# SY_HR08_MCU_CTL_V1_1.net
KiCad netlist of a schematic drawn in Altium Designer
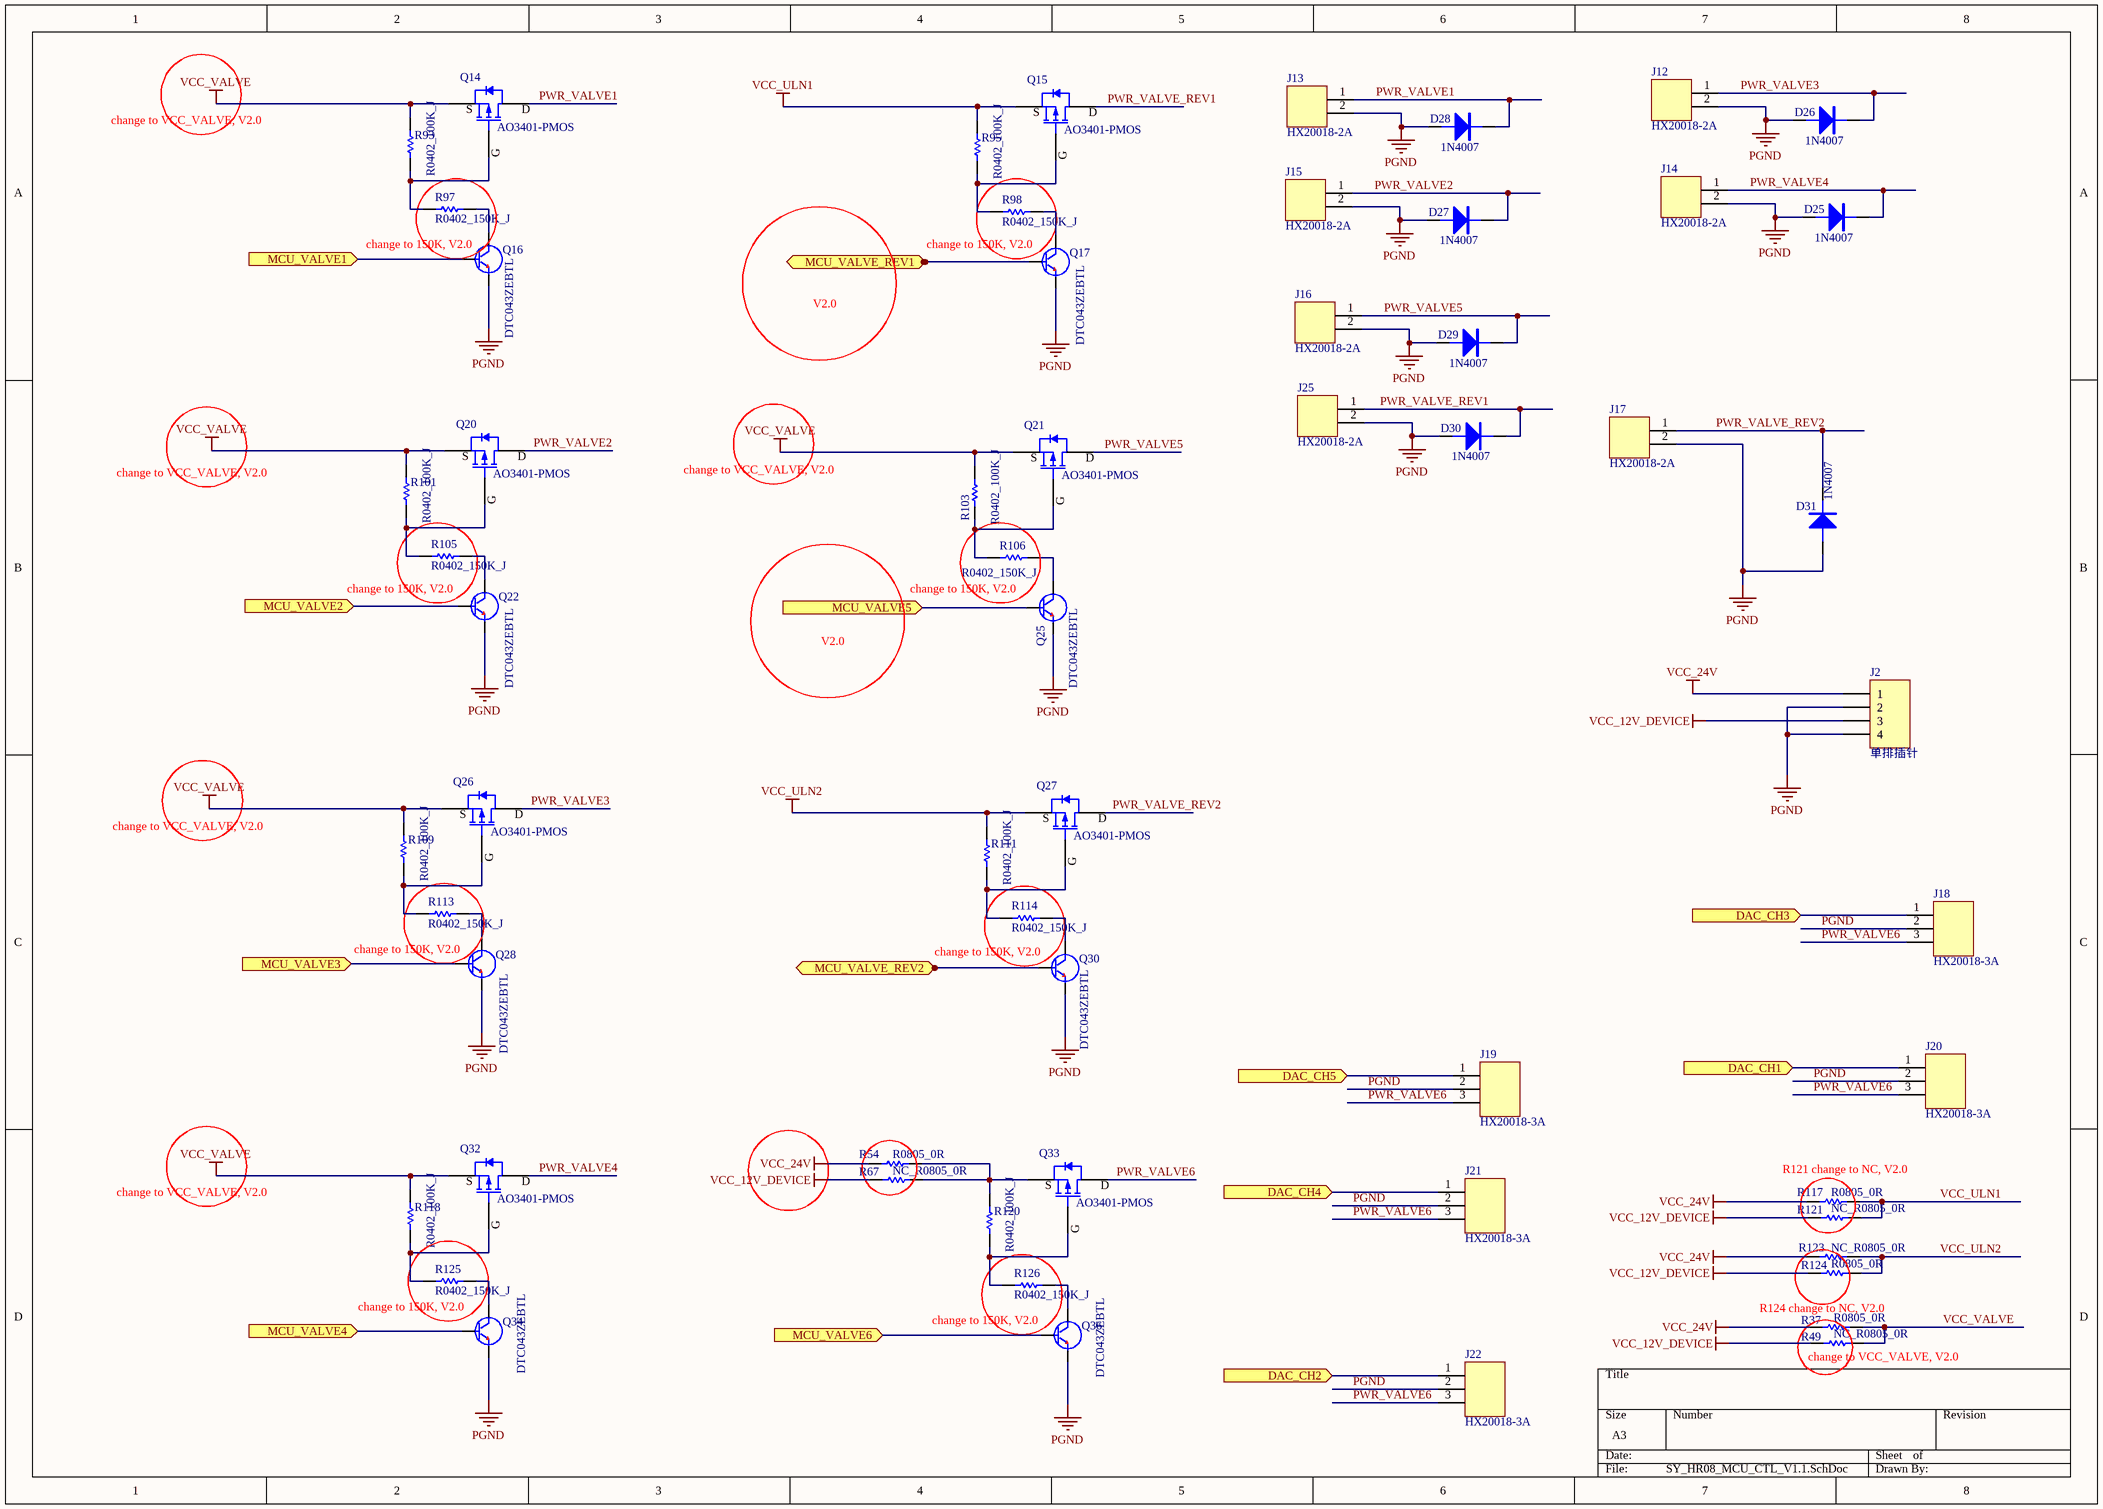
[diagram p0: SY_HR08_MCU_CTL_V1.1.SchDoc]

(export (version "E")
  (design (tool "Eeschema 10.0.6"))
  (components
    (comp (ref "D25")
      (value "1N4007")
      (footprint "1N4007")
      (description "1N4007 整流二极管 1A 1000V")
      (libsource (lib "zhangky_sch") (part "1N4007"))
    )
    (comp (ref "D26")
      (value "1N4007")
      (footprint "1N4007")
      (description "1N4007 整流二极管 1A 1000V")
      (libsource (lib "zhangky_sch") (part "1N4007"))
    )
    (comp (ref "D27")
      (value "1N4007")
      (footprint "1N4007")
      (description "1N4007 整流二极管 1A 1000V")
      (libsource (lib "zhangky_sch") (part "1N4007"))
    )
    (comp (ref "D28")
      (value "1N4007")
      (footprint "1N4007")
      (description "1N4007 整流二极管 1A 1000V")
      (libsource (lib "zhangky_sch") (part "1N4007"))
    )
    (comp (ref "D29")
      (value "1N4007")
      (footprint "1N4007")
      (description "1N4007 整流二极管 1A 1000V")
      (libsource (lib "zhangky_sch") (part "1N4007"))
    )
    (comp (ref "D30")
      (value "1N4007")
      (footprint "1N4007")
      (description "1N4007 整流二极管 1A 1000V")
      (libsource (lib "zhangky_sch") (part "1N4007"))
    )
    (comp (ref "D31")
      (value "1N4007")
      (footprint "1N4007")
      (description "1N4007 整流二极管 1A 1000V")
      (libsource (lib "zhangky_sch") (part "1N4007"))
    )
    (comp (ref "J2")
      (value "单排插针")
      (footprint "CON1X4(2.54mm)")
      (description "Header, 4-Pin")
      (fields (field (name "PUBLISHER") "Altium Limited"))
      (libsource (lib "YS-F1Pro开发板主板") (part "Header 4"))
    )
    (comp (ref "J12")
      (value "HX20018-2A")
      (footprint "HX20018-2A")
      (description "HX20018-2A  2.0mm")
      (libsource (lib "zhangky_sch") (part "HX20018-2A"))
    )
    (comp (ref "J13")
      (value "HX20018-2A")
      (footprint "HX20018-2A")
      (description "HX20018-2A  2.0mm")
      (libsource (lib "zhangky_sch") (part "HX20018-2A"))
    )
    (comp (ref "J14")
      (value "HX20018-2A")
      (footprint "HX20018-2A")
      (description "HX20018-2A  2.0mm")
      (libsource (lib "zhangky_sch") (part "HX20018-2A"))
    )
    (comp (ref "J15")
      (value "HX20018-2A")
      (footprint "HX20018-2A")
      (description "HX20018-2A  2.0mm")
      (libsource (lib "zhangky_sch") (part "HX20018-2A"))
    )
    (comp (ref "J16")
      (value "HX20018-2A")
      (footprint "HX20018-2A")
      (description "HX20018-2A  2.0mm")
      (libsource (lib "zhangky_sch") (part "HX20018-2A"))
    )
    (comp (ref "J17")
      (value "HX20018-2A")
      (footprint "HX20018-2A")
      (description "HX20018-2A  2.0mm")
      (libsource (lib "zhangky_sch") (part "HX20018-2A"))
    )
    (comp (ref "J18")
      (value "HX20018-3A")
      (footprint "HX20018-3A")
      (description "HX20018-3A  2.0mm")
      (libsource (lib "zhangky_sch") (part "HX20018-3A"))
    )
    (comp (ref "J19")
      (value "HX20018-3A")
      (footprint "HX20018-3A")
      (description "HX20018-3A  2.0mm")
      (libsource (lib "zhangky_sch") (part "HX20018-3A"))
    )
    (comp (ref "J20")
      (value "HX20018-3A")
      (footprint "HX20018-3A")
      (description "HX20018-3A  2.0mm")
      (libsource (lib "zhangky_sch") (part "HX20018-3A"))
    )
    (comp (ref "J21")
      (value "HX20018-3A")
      (footprint "HX20018-3A")
      (description "HX20018-3A  2.0mm")
      (libsource (lib "zhangky_sch") (part "HX20018-3A"))
    )
    (comp (ref "J22")
      (value "HX20018-3A")
      (footprint "HX20018-3A")
      (description "HX20018-3A  2.0mm")
      (libsource (lib "zhangky_sch") (part "HX20018-3A"))
    )
    (comp (ref "J25")
      (value "HX20018-2A")
      (footprint "HX20018-2A")
      (description "HX20018-2A  2.0mm")
      (libsource (lib "zhangky_sch") (part "HX20018-2A"))
    )
    (comp (ref "Q14")
      (value "AO3401-PMOS")
      (footprint "AO3400")
      (libsource (lib "zhangky_sch") (part "AO3401-PMOS"))
    )
    (comp (ref "Q15")
      (value "AO3401-PMOS")
      (footprint "AO3400")
      (libsource (lib "zhangky_sch") (part "AO3401-PMOS"))
    )
    (comp (ref "Q16")
      (value "DTC043ZEBTL")
      (footprint "DTC043ZEBTL$2F$$2F$DTC143ZE$2F$$2F$LDTC143ZET1G")
      (description "NPN三极管_100mA_EMT3F")
      (libsource (lib "zhangky_sch") (part "DTC043ZEBTL"))
    )
    (comp (ref "Q17")
      (value "DTC043ZEBTL")
      (footprint "DTC043ZEBTL$2F$$2F$DTC143ZE$2F$$2F$LDTC143ZET1G")
      (description "NPN三极管_100mA_EMT3F")
      (libsource (lib "zhangky_sch") (part "DTC043ZEBTL"))
    )
    (comp (ref "Q20")
      (value "AO3401-PMOS")
      (footprint "AO3400")
      (libsource (lib "zhangky_sch") (part "AO3401-PMOS"))
    )
    (comp (ref "Q21")
      (value "AO3401-PMOS")
      (footprint "AO3400")
      (libsource (lib "zhangky_sch") (part "AO3401-PMOS"))
    )
    (comp (ref "Q22")
      (value "DTC043ZEBTL")
      (footprint "DTC043ZEBTL$2F$$2F$DTC143ZE$2F$$2F$LDTC143ZET1G")
      (description "NPN三极管_100mA_EMT3F")
      (libsource (lib "zhangky_sch") (part "DTC043ZEBTL"))
    )
    (comp (ref "Q25")
      (value "DTC043ZEBTL")
      (footprint "DTC043ZEBTL$2F$$2F$DTC143ZE$2F$$2F$LDTC143ZET1G")
      (description "NPN三极管_100mA_EMT3F")
      (libsource (lib "zhangky_sch") (part "DTC043ZEBTL"))
    )
    (comp (ref "Q26")
      (value "AO3401-PMOS")
      (footprint "AO3400")
      (libsource (lib "zhangky_sch") (part "AO3401-PMOS"))
    )
    (comp (ref "Q27")
      (value "AO3401-PMOS")
      (footprint "AO3400")
      (libsource (lib "zhangky_sch") (part "AO3401-PMOS"))
    )
    (comp (ref "Q28")
      (value "DTC043ZEBTL")
      (footprint "DTC043ZEBTL$2F$$2F$DTC143ZE$2F$$2F$LDTC143ZET1G")
      (description "NPN三极管_100mA_EMT3F")
      (libsource (lib "zhangky_sch") (part "DTC043ZEBTL"))
    )
    (comp (ref "Q30")
      (value "DTC043ZEBTL")
      (footprint "DTC043ZEBTL$2F$$2F$DTC143ZE$2F$$2F$LDTC143ZET1G")
      (description "NPN三极管_100mA_EMT3F")
      (libsource (lib "zhangky_sch") (part "DTC043ZEBTL"))
    )
    (comp (ref "Q32")
      (value "AO3401-PMOS")
      (footprint "AO3400")
      (libsource (lib "zhangky_sch") (part "AO3401-PMOS"))
    )
    (comp (ref "Q33")
      (value "AO3401-PMOS")
      (footprint "AO3400")
      (libsource (lib "zhangky_sch") (part "AO3401-PMOS"))
    )
    (comp (ref "Q34")
      (value "DTC043ZEBTL")
      (footprint "DTC043ZEBTL$2F$$2F$DTC143ZE$2F$$2F$LDTC143ZET1G")
      (description "NPN三极管_100mA_EMT3F")
      (libsource (lib "zhangky_sch") (part "DTC043ZEBTL"))
    )
    (comp (ref "Q36")
      (value "DTC043ZEBTL")
      (footprint "DTC043ZEBTL$2F$$2F$DTC143ZE$2F$$2F$LDTC143ZET1G")
      (description "NPN三极管_100mA_EMT3F")
      (libsource (lib "zhangky_sch") (part "DTC043ZEBTL"))
    )
    (comp (ref "R37")
      (value "R0805_0R")
      (footprint "RES0805")
      (description "电阻0R(0805-0.125W-J)")
      (libsource (lib "zhangky_sch") (part "R0805_0R"))
    )
    (comp (ref "R49")
      (value "NC_R0805_0R")
      (footprint "RES0805")
      (description "电阻0R(0805-0.125W-J)")
      (libsource (lib "zhangky_sch") (part "R0805_0R"))
    )
    (comp (ref "R54")
      (value "R0805_0R")
      (footprint "RES0805")
      (description "电阻0R(0805-0.125W-J)")
      (libsource (lib "zhangky_sch") (part "R0805_0R"))
    )
    (comp (ref "R67")
      (value "NC_R0805_0R")
      (footprint "RES0805")
      (description "电阻0R(0805-0.125W-J)")
      (libsource (lib "zhangky_sch") (part "R0805_0R"))
    )
    (comp (ref "R93")
      (value "R0402_100K_J")
      (footprint "RES0402_HQ")
      (description "电阻100K(0402-0.0625W-J)")
      (libsource (lib "zhangky_sch") (part "R0402_100K_J"))
    )
    (comp (ref "R95")
      (value "R0402_100K_J")
      (footprint "RES0402_HQ")
      (description "电阻100K(0402-0.0625W-J)")
      (libsource (lib "zhangky_sch") (part "R0402_100K_J"))
    )
    (comp (ref "R97")
      (value "R0402_150K_J")
      (footprint "RES0402_HQ")
      (description "电阻100K(0402-0.0625W-J)")
      (libsource (lib "zhangky_sch") (part "R0402_100K_J"))
    )
    (comp (ref "R98")
      (value "R0402_150K_J")
      (footprint "RES0402_HQ")
      (description "电阻100K(0402-0.0625W-J)")
      (libsource (lib "zhangky_sch") (part "R0402_100K_J"))
    )
    (comp (ref "R101")
      (value "R0402_100K_J")
      (footprint "RES0402_HQ")
      (description "电阻100K(0402-0.0625W-J)")
      (libsource (lib "zhangky_sch") (part "R0402_100K_J"))
    )
    (comp (ref "R103")
      (value "R0402_100K_J")
      (footprint "RES0402_HQ")
      (description "电阻100K(0402-0.0625W-J)")
      (libsource (lib "zhangky_sch") (part "R0402_100K_J"))
    )
    (comp (ref "R105")
      (value "R0402_150K_J")
      (footprint "RES0402_HQ")
      (description "电阻100K(0402-0.0625W-J)")
      (libsource (lib "zhangky_sch") (part "R0402_100K_J"))
    )
    (comp (ref "R106")
      (value "R0402_150K_J")
      (footprint "RES0402_HQ")
      (description "电阻100K(0402-0.0625W-J)")
      (libsource (lib "zhangky_sch") (part "R0402_100K_J"))
    )
    (comp (ref "R109")
      (value "R0402_100K_J")
      (footprint "RES0402_HQ")
      (description "电阻100K(0402-0.0625W-J)")
      (libsource (lib "zhangky_sch") (part "R0402_100K_J"))
    )
    (comp (ref "R111")
      (value "R0402_100K_J")
      (footprint "RES0402_HQ")
      (description "电阻100K(0402-0.0625W-J)")
      (libsource (lib "zhangky_sch") (part "R0402_100K_J"))
    )
    (comp (ref "R113")
      (value "R0402_150K_J")
      (footprint "RES0402_HQ")
      (description "电阻100K(0402-0.0625W-J)")
      (libsource (lib "zhangky_sch") (part "R0402_100K_J"))
    )
    (comp (ref "R114")
      (value "R0402_150K_J")
      (footprint "RES0402_HQ")
      (description "电阻100K(0402-0.0625W-J)")
      (libsource (lib "zhangky_sch") (part "R0402_100K_J"))
    )
    (comp (ref "R117")
      (value "R0805_0R")
      (footprint "RES0805")
      (description "电阻0R(0805-0.125W-J)")
      (libsource (lib "zhangky_sch") (part "R0805_0R"))
    )
    (comp (ref "R118")
      (value "R0402_100K_J")
      (footprint "RES0402_HQ")
      (description "电阻100K(0402-0.0625W-J)")
      (libsource (lib "zhangky_sch") (part "R0402_100K_J"))
    )
    (comp (ref "R120")
      (value "R0402_100K_J")
      (footprint "RES0402_HQ")
      (description "电阻100K(0402-0.0625W-J)")
      (libsource (lib "zhangky_sch") (part "R0402_100K_J"))
    )
    (comp (ref "R121")
      (value "NC_R0805_0R")
      (footprint "RES0805")
      (description "电阻0R(0805-0.125W-J)")
      (libsource (lib "zhangky_sch") (part "R0805_0R"))
    )
    (comp (ref "R123")
      (value "NC_R0805_0R")
      (footprint "RES0805")
      (description "电阻0R(0805-0.125W-J)")
      (libsource (lib "zhangky_sch") (part "R0805_0R"))
    )
    (comp (ref "R124")
      (value "R0805_0R")
      (footprint "RES0805")
      (description "电阻0R(0805-0.125W-J)")
      (libsource (lib "zhangky_sch") (part "R0805_0R"))
    )
    (comp (ref "R125")
      (value "R0402_150K_J")
      (footprint "RES0402_HQ")
      (description "电阻100K(0402-0.0625W-J)")
      (libsource (lib "zhangky_sch") (part "R0402_100K_J"))
    )
    (comp (ref "R126")
      (value "R0402_150K_J")
      (footprint "RES0402_HQ")
      (description "电阻100K(0402-0.0625W-J)")
      (libsource (lib "zhangky_sch") (part "R0402_100K_J"))
    )
  )
  (nets
    (net (code "1") (name "/DAC_CH1") (class "Default")
      (node (ref "J20") (pin "1") (pinfunction "1_1") (pintype "passive"))
    )
    (net (code "2") (name "/DAC_CH2") (class "Default")
      (node (ref "J22") (pin "1") (pinfunction "1_1") (pintype "passive"))
    )
    (net (code "3") (name "/DAC_CH3") (class "Default")
      (node (ref "J18") (pin "1") (pinfunction "1_1") (pintype "passive"))
    )
    (net (code "4") (name "/DAC_CH4") (class "Default")
      (node (ref "J21") (pin "1") (pinfunction "1_1") (pintype "passive"))
    )
    (net (code "5") (name "/DAC_CH5") (class "Default")
      (node (ref "J19") (pin "1") (pinfunction "1_1") (pintype "passive"))
    )
    (net (code "6") (name "/MCU_VALVE1") (class "Default")
      (node (ref "Q16") (pin "1") (pinfunction "B_1") (pintype "passive"))
    )
    (net (code "7") (name "/MCU_VALVE2") (class "Default")
      (node (ref "Q22") (pin "1") (pinfunction "B_1") (pintype "passive"))
    )
    (net (code "8") (name "/MCU_VALVE3") (class "Default")
      (node (ref "Q28") (pin "1") (pinfunction "B_1") (pintype "passive"))
    )
    (net (code "9") (name "/MCU_VALVE4") (class "Default")
      (node (ref "Q34") (pin "1") (pinfunction "B_1") (pintype "passive"))
    )
    (net (code "10") (name "/MCU_VALVE5") (class "Default")
      (node (ref "Q25") (pin "1") (pinfunction "B_1") (pintype "passive"))
    )
    (net (code "11") (name "/MCU_VALVE6") (class "Default")
      (node (ref "Q36") (pin "1") (pinfunction "B_1") (pintype "passive"))
    )
    (net (code "12") (name "/MCU_VALVE_REV1") (class "Default")
      (node (ref "Q17") (pin "1") (pinfunction "B_1") (pintype "passive"))
    )
    (net (code "13") (name "/MCU_VALVE_REV2") (class "Default")
      (node (ref "Q30") (pin "1") (pinfunction "B_1") (pintype "passive"))
    )
    (net (code "14") (name "/PWR_VALVE1") (class "Default")
      (node (ref "D28") (pin "1") (pinfunction "1_1") (pintype "passive"))
      (node (ref "J13") (pin "1") (pinfunction "1_1") (pintype "passive"))
      (node (ref "Q14") (pin "3") (pinfunction "D_3") (pintype "passive"))
    )
    (net (code "15") (name "/PWR_VALVE2") (class "Default")
      (node (ref "D27") (pin "1") (pinfunction "1_1") (pintype "passive"))
      (node (ref "J15") (pin "1") (pinfunction "1_1") (pintype "passive"))
      (node (ref "Q20") (pin "3") (pinfunction "D_3") (pintype "passive"))
    )
    (net (code "16") (name "/PWR_VALVE3") (class "Default")
      (node (ref "D26") (pin "1") (pinfunction "1_1") (pintype "passive"))
      (node (ref "J12") (pin "1") (pinfunction "1_1") (pintype "passive"))
      (node (ref "Q26") (pin "3") (pinfunction "D_3") (pintype "passive"))
    )
    (net (code "17") (name "/PWR_VALVE4") (class "Default")
      (node (ref "D25") (pin "1") (pinfunction "1_1") (pintype "passive"))
      (node (ref "J14") (pin "1") (pinfunction "1_1") (pintype "passive"))
      (node (ref "Q32") (pin "3") (pinfunction "D_3") (pintype "passive"))
    )
    (net (code "18") (name "/PWR_VALVE5") (class "Default")
      (node (ref "D29") (pin "1") (pinfunction "1_1") (pintype "passive"))
      (node (ref "J16") (pin "1") (pinfunction "1_1") (pintype "passive"))
      (node (ref "Q21") (pin "3") (pinfunction "D_3") (pintype "passive"))
    )
    (net (code "19") (name "/PWR_VALVE6") (class "Default")
      (node (ref "J18") (pin "3") (pinfunction "3_3") (pintype "passive"))
      (node (ref "J19") (pin "3") (pinfunction "3_3") (pintype "passive"))
      (node (ref "J20") (pin "3") (pinfunction "3_3") (pintype "passive"))
      (node (ref "J21") (pin "3") (pinfunction "3_3") (pintype "passive"))
      (node (ref "J22") (pin "3") (pinfunction "3_3") (pintype "passive"))
      (node (ref "Q33") (pin "3") (pinfunction "D_3") (pintype "passive"))
    )
    (net (code "20") (name "/PWR_VALVE_REV1") (class "Default")
      (node (ref "D30") (pin "1") (pinfunction "1_1") (pintype "passive"))
      (node (ref "J25") (pin "1") (pinfunction "1_1") (pintype "passive"))
      (node (ref "Q15") (pin "3") (pinfunction "D_3") (pintype "passive"))
    )
    (net (code "21") (name "/PWR_VALVE_REV2") (class "Default")
      (node (ref "D31") (pin "1") (pinfunction "1_1") (pintype "passive"))
      (node (ref "J17") (pin "1") (pinfunction "1_1") (pintype "passive"))
      (node (ref "Q27") (pin "3") (pinfunction "D_3") (pintype "passive"))
    )
    (net (code "22") (name "Net-(Q14-G)") (class "Default")
      (node (ref "Q14") (pin "1") (pinfunction "G_1") (pintype "passive"))
      (node (ref "R93") (pin "1") (pinfunction "1_1") (pintype "passive"))
      (node (ref "R97") (pin "2") (pinfunction "2_2") (pintype "passive"))
    )
    (net (code "23") (name "Net-(Q15-G)") (class "Default")
      (node (ref "Q15") (pin "1") (pinfunction "G_1") (pintype "passive"))
      (node (ref "R95") (pin "1") (pinfunction "1_1") (pintype "passive"))
      (node (ref "R98") (pin "2") (pinfunction "2_2") (pintype "passive"))
    )
    (net (code "24") (name "Net-(Q16-C)") (class "Default")
      (node (ref "Q16") (pin "3") (pinfunction "C_3") (pintype "passive"))
      (node (ref "R97") (pin "1") (pinfunction "1_1") (pintype "passive"))
    )
    (net (code "25") (name "Net-(Q17-C)") (class "Default")
      (node (ref "Q17") (pin "3") (pinfunction "C_3") (pintype "passive"))
      (node (ref "R98") (pin "1") (pinfunction "1_1") (pintype "passive"))
    )
    (net (code "26") (name "Net-(Q20-G)") (class "Default")
      (node (ref "Q20") (pin "1") (pinfunction "G_1") (pintype "passive"))
      (node (ref "R101") (pin "1") (pinfunction "1_1") (pintype "passive"))
      (node (ref "R105") (pin "2") (pinfunction "2_2") (pintype "passive"))
    )
    (net (code "27") (name "Net-(Q21-G)") (class "Default")
      (node (ref "Q21") (pin "1") (pinfunction "G_1") (pintype "passive"))
      (node (ref "R103") (pin "1") (pinfunction "1_1") (pintype "passive"))
      (node (ref "R106") (pin "2") (pinfunction "2_2") (pintype "passive"))
    )
    (net (code "28") (name "Net-(Q22-C)") (class "Default")
      (node (ref "Q22") (pin "3") (pinfunction "C_3") (pintype "passive"))
      (node (ref "R105") (pin "1") (pinfunction "1_1") (pintype "passive"))
    )
    (net (code "29") (name "Net-(Q25-C)") (class "Default")
      (node (ref "Q25") (pin "3") (pinfunction "C_3") (pintype "passive"))
      (node (ref "R106") (pin "1") (pinfunction "1_1") (pintype "passive"))
    )
    (net (code "30") (name "Net-(Q26-G)") (class "Default")
      (node (ref "Q26") (pin "1") (pinfunction "G_1") (pintype "passive"))
      (node (ref "R109") (pin "1") (pinfunction "1_1") (pintype "passive"))
      (node (ref "R113") (pin "2") (pinfunction "2_2") (pintype "passive"))
    )
    (net (code "31") (name "Net-(Q27-G)") (class "Default")
      (node (ref "Q27") (pin "1") (pinfunction "G_1") (pintype "passive"))
      (node (ref "R111") (pin "1") (pinfunction "1_1") (pintype "passive"))
      (node (ref "R114") (pin "2") (pinfunction "2_2") (pintype "passive"))
    )
    (net (code "32") (name "Net-(Q28-C)") (class "Default")
      (node (ref "Q28") (pin "3") (pinfunction "C_3") (pintype "passive"))
      (node (ref "R113") (pin "1") (pinfunction "1_1") (pintype "passive"))
    )
    (net (code "33") (name "Net-(Q30-C)") (class "Default")
      (node (ref "Q30") (pin "3") (pinfunction "C_3") (pintype "passive"))
      (node (ref "R114") (pin "1") (pinfunction "1_1") (pintype "passive"))
    )
    (net (code "34") (name "Net-(Q32-G)") (class "Default")
      (node (ref "Q32") (pin "1") (pinfunction "G_1") (pintype "passive"))
      (node (ref "R118") (pin "1") (pinfunction "1_1") (pintype "passive"))
      (node (ref "R125") (pin "2") (pinfunction "2_2") (pintype "passive"))
    )
    (net (code "35") (name "Net-(Q33-G)") (class "Default")
      (node (ref "Q33") (pin "1") (pinfunction "G_1") (pintype "passive"))
      (node (ref "R120") (pin "1") (pinfunction "1_1") (pintype "passive"))
      (node (ref "R126") (pin "2") (pinfunction "2_2") (pintype "passive"))
    )
    (net (code "36") (name "Net-(Q33-S)") (class "Default")
      (node (ref "Q33") (pin "2") (pinfunction "S_2") (pintype "passive"))
      (node (ref "R120") (pin "2") (pinfunction "2_2") (pintype "passive"))
      (node (ref "R54") (pin "2") (pinfunction "2_2") (pintype "passive"))
      (node (ref "R67") (pin "2") (pinfunction "2_2") (pintype "passive"))
    )
    (net (code "37") (name "Net-(Q34-C)") (class "Default")
      (node (ref "Q34") (pin "3") (pinfunction "C_3") (pintype "passive"))
      (node (ref "R125") (pin "1") (pinfunction "1_1") (pintype "passive"))
    )
    (net (code "38") (name "Net-(Q36-C)") (class "Default")
      (node (ref "Q36") (pin "3") (pinfunction "C_3") (pintype "passive"))
      (node (ref "R126") (pin "1") (pinfunction "1_1") (pintype "passive"))
    )
    (net (code "39") (name "PGND") (class "Default")
      (node (ref "D25") (pin "2") (pinfunction "2_2") (pintype "passive"))
      (node (ref "D26") (pin "2") (pinfunction "2_2") (pintype "passive"))
      (node (ref "D27") (pin "2") (pinfunction "2_2") (pintype "passive"))
      (node (ref "D28") (pin "2") (pinfunction "2_2") (pintype "passive"))
      (node (ref "D29") (pin "2") (pinfunction "2_2") (pintype "passive"))
      (node (ref "D30") (pin "2") (pinfunction "2_2") (pintype "passive"))
      (node (ref "D31") (pin "2") (pinfunction "2_2") (pintype "passive"))
      (node (ref "J12") (pin "2") (pinfunction "2_2") (pintype "passive"))
      (node (ref "J13") (pin "2") (pinfunction "2_2") (pintype "passive"))
      (node (ref "J14") (pin "2") (pinfunction "2_2") (pintype "passive"))
      (node (ref "J15") (pin "2") (pinfunction "2_2") (pintype "passive"))
      (node (ref "J16") (pin "2") (pinfunction "2_2") (pintype "passive"))
      (node (ref "J17") (pin "2") (pinfunction "2_2") (pintype "passive"))
      (node (ref "J18") (pin "2") (pinfunction "2_2") (pintype "passive"))
      (node (ref "J19") (pin "2") (pinfunction "2_2") (pintype "passive"))
      (node (ref "J2") (pin "2") (pinfunction "2_2") (pintype "passive"))
      (node (ref "J2") (pin "4") (pinfunction "4_4") (pintype "passive"))
      (node (ref "J20") (pin "2") (pinfunction "2_2") (pintype "passive"))
      (node (ref "J21") (pin "2") (pinfunction "2_2") (pintype "passive"))
      (node (ref "J22") (pin "2") (pinfunction "2_2") (pintype "passive"))
      (node (ref "J25") (pin "2") (pinfunction "2_2") (pintype "passive"))
      (node (ref "Q16") (pin "2") (pinfunction "E_2") (pintype "passive"))
      (node (ref "Q17") (pin "2") (pinfunction "E_2") (pintype "passive"))
      (node (ref "Q22") (pin "2") (pinfunction "E_2") (pintype "passive"))
      (node (ref "Q25") (pin "2") (pinfunction "E_2") (pintype "passive"))
      (node (ref "Q28") (pin "2") (pinfunction "E_2") (pintype "passive"))
      (node (ref "Q30") (pin "2") (pinfunction "E_2") (pintype "passive"))
      (node (ref "Q34") (pin "2") (pinfunction "E_2") (pintype "passive"))
      (node (ref "Q36") (pin "2") (pinfunction "E_2") (pintype "passive"))
    )
    (net (code "40") (name "VCC_12V_DEVICE") (class "Default")
      (node (ref "J2") (pin "3") (pinfunction "3_3") (pintype "passive"))
      (node (ref "R121") (pin "1") (pinfunction "1_1") (pintype "passive"))
      (node (ref "R124") (pin "1") (pinfunction "1_1") (pintype "passive"))
      (node (ref "R49") (pin "1") (pinfunction "1_1") (pintype "passive"))
      (node (ref "R67") (pin "1") (pinfunction "1_1") (pintype "passive"))
    )
    (net (code "41") (name "VCC_24V") (class "Default")
      (node (ref "J2") (pin "1") (pinfunction "1_1") (pintype "passive"))
      (node (ref "R117") (pin "1") (pinfunction "1_1") (pintype "passive"))
      (node (ref "R123") (pin "1") (pinfunction "1_1") (pintype "passive"))
      (node (ref "R37") (pin "1") (pinfunction "1_1") (pintype "passive"))
      (node (ref "R54") (pin "1") (pinfunction "1_1") (pintype "passive"))
    )
    (net (code "42") (name "VCC_ULN1") (class "Default")
      (node (ref "Q15") (pin "2") (pinfunction "S_2") (pintype "passive"))
      (node (ref "R117") (pin "2") (pinfunction "2_2") (pintype "passive"))
      (node (ref "R121") (pin "2") (pinfunction "2_2") (pintype "passive"))
      (node (ref "R95") (pin "2") (pinfunction "2_2") (pintype "passive"))
    )
    (net (code "43") (name "VCC_ULN2") (class "Default")
      (node (ref "Q27") (pin "2") (pinfunction "S_2") (pintype "passive"))
      (node (ref "R111") (pin "2") (pinfunction "2_2") (pintype "passive"))
      (node (ref "R123") (pin "2") (pinfunction "2_2") (pintype "passive"))
      (node (ref "R124") (pin "2") (pinfunction "2_2") (pintype "passive"))
    )
    (net (code "44") (name "VCC_VALVE") (class "Default")
      (node (ref "Q14") (pin "2") (pinfunction "S_2") (pintype "passive"))
      (node (ref "Q20") (pin "2") (pinfunction "S_2") (pintype "passive"))
      (node (ref "Q21") (pin "2") (pinfunction "S_2") (pintype "passive"))
      (node (ref "Q26") (pin "2") (pinfunction "S_2") (pintype "passive"))
      (node (ref "Q32") (pin "2") (pinfunction "S_2") (pintype "passive"))
      (node (ref "R101") (pin "2") (pinfunction "2_2") (pintype "passive"))
      (node (ref "R103") (pin "2") (pinfunction "2_2") (pintype "passive"))
      (node (ref "R109") (pin "2") (pinfunction "2_2") (pintype "passive"))
      (node (ref "R118") (pin "2") (pinfunction "2_2") (pintype "passive"))
      (node (ref "R37") (pin "2") (pinfunction "2_2") (pintype "passive"))
      (node (ref "R49") (pin "2") (pinfunction "2_2") (pintype "passive"))
      (node (ref "R93") (pin "2") (pinfunction "2_2") (pintype "passive"))
    )
  )
)
